# Main.net
KiCad netlist of a schematic drawn in Altium Designer
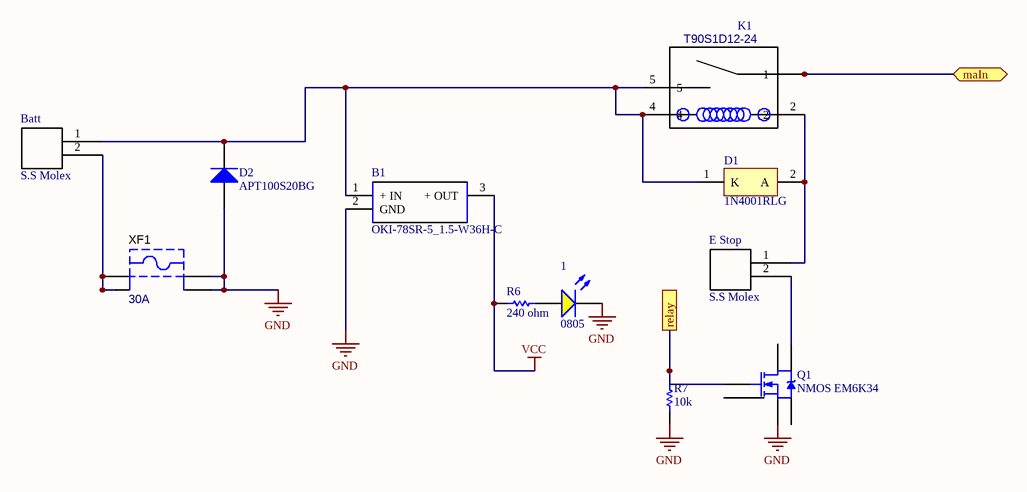
[diagram p0: Main.SchDoc]

(export (version "E")
  (design (tool "Eeschema 10.0.6"))
  (components
    (comp (ref "1")
      (value "0805")
      (footprint "LTST-C170YKT_V")
      (description "LED YELLOW CLEAR 0805 SMD")
      (fields (field (name "PARTNUMBER") "LTST-C170YKT"))
      (libsource (lib "Altium Content Vault") (part "LED_YELLOW_AC"))
    )
    (comp (ref "B1")
      (value "OKI-78SR-5_1.5-W36H-C")
      (footprint "OKI-78SR-HORIZONTAL")
      (description "Switching Regulator 7-36Vin 5Vo 1.5A Non-Isolated DC-DC Converter, 5V dc Output, 1.5A")
      (fields
        (field (name "MOUSER PART NUMBER") "580-OKI78SR51.5W36HC")
        (field (name "MANUFACTURER_PART_NUMBER") "OKI-78SR-5/1.5-W36H-C")
      )
      (libsource (lib "OKI-78SR-5_1.5-W36H-C") (part "OKI-78SR-5_1.5-W36H-C"))
    )
    (comp (ref "Batt")
      (value "S.S Molex")
      (footprint "1510482204")
      (description "Molex 6.5MM 2 pin connector, used for power connections. P/N 1510482204 and similar models.")
      (libsource (lib "24v connector") (part "Molex 6.5MM 2 pin connector"))
    )
    (comp (ref "D1")
      (value "1N4001RLG")
      (footprint "ONSC-AXIAL_LEAD-2-59-10_P")
      (description "Standard Recovery Rectifier, 2-Pin Axial_Lead, Pb-Free, Tape and Reel")
      (fields (field (name "MANUFACTURER") "On Semiconductor"))
      (libsource (lib "Altium Content Vault") (part "ONSC-D-K1A2-2_A"))
    )
    (comp (ref "D2")
      (value "APT100S20BG")
      (footprint "SMC")
      (description "Default Diode")
      (fields
        (field (name "PUBLISHER") "Altium Limited")
        (field (name "COMPONENTLINK1URL") "file:///C:/Users/Me/Downloads/Microsemi_APT100S20BG_High-Voltage_Schottky_Diode_Datasheet_D%20(1).PDF")
      )
      (libsource (lib "Miscellaneous Devices") (part "Diode"))
    )
    (comp (ref "E Stop")
      (value "S.S Molex")
      (footprint "1510482204")
      (description "Molex 6.5MM 2 pin connector, used for power connections. P/N 1510482204 and similar models.")
      (libsource (lib "24v connector") (part "Molex 6.5MM 2 pin connector"))
    )
    (comp (ref "K1")
      (value "T90S1D12-24")
      (footprint "TE_1-1393209-6")
      (fields (field (name "MF") "TE Connectivity"))
      (libsource (lib "1-1393209-6") (part "1-1393209-6"))
    )
    (comp (ref "Q1")
      (value "NMOS EM6K34")
      (footprint "*SOT50P160X55-6N")
      (description "N-Channel Power MOSFET")
      (fields (field (name "PUBLISHER") "Altium Limited"))
      (libsource (lib "Miscellaneous Devices") (part "NMOS-2"))
    )
    (comp (ref "R6")
      (value "240 ohm")
      (footprint "RESC0805(2012)_N")
      (description "160R 0.125W 1% 0805 (2012 Metric)  SMD")
      (fields (field (name "TOLERANCE") "1 %") (field (name "POWER") "0.125 W"))
      (libsource (lib "Altium Content Vault") (part "RES"))
    )
    (comp (ref "R7")
      (value "10k")
      (footprint "RESC0805(2012)_N")
      (description "160R 0.125W 1% 0805 (2012 Metric)  SMD")
      (fields (field (name "TOLERANCE") "1 %") (field (name "POWER") "0.125 W"))
      (libsource (lib "Altium Content Vault") (part "RES"))
    )
    (comp (ref "XF1")
      (value "30A")
      (footprint "KSTN-3568_V")
      (description "Fuse Holder, 30")
      (fields (field (name "MANUFACTURER") "Keystone"))
      (libsource (lib "Altium Content Vault") (part "FUSE_HOLDER-4"))
    )
  )
  (nets
    (net (code "1") (name "/maIn") (class "Default")
      (node (ref "K1") (pin "1") (pinfunction "1_1") (pintype "passive"))
      (node (ref "K1") (pin "3") (pinfunction "1_3") (pintype "passive"))
    )
    (net (code "2") (name "/relay") (class "Default")
      (node (ref "Q1") (pin "5") (pinfunction "G_5") (pintype "passive"))
      (node (ref "R7") (pin "2") (pinfunction "2_2") (pintype "passive"))
    )
    (net (code "3") (name "GND") (class "Default")
      (node (ref "1") (pin "C") (pinfunction "C_C") (pintype "passive"))
      (node (ref "B1") (pin "2") (pinfunction "GND_2") (pintype "passive"))
      (node (ref "D2") (pin "3") (pinfunction "A_3") (pintype "passive"))
      (node (ref "Q1") (pin "4") (pinfunction "S_4") (pintype "passive"))
      (node (ref "R7") (pin "1") (pinfunction "1_1") (pintype "passive"))
      (node (ref "XF1") (pin "3") (pinfunction "3_3") (pintype "passive"))
      (node (ref "XF1") (pin "4") (pinfunction "4_4") (pintype "passive"))
    )
    (net (code "4") (name "Net-(B1-+_IN)") (class "Default")
      (node (ref "B1") (pin "1") (pinfunction "+_IN_1") (pintype "passive"))
      (node (ref "Batt") (pin "1") (pintype "passive"))
      (node (ref "D1") (pin "1") (pinfunction "K_1") (pintype "passive"))
      (node (ref "D2") (pin "2") (pinfunction "K_2") (pintype "passive"))
      (node (ref "K1") (pin "4") (pinfunction "4_4") (pintype "passive"))
      (node (ref "K1") (pin "5") (pinfunction "5_5") (pintype "passive"))
    )
    (net (code "5") (name "Net-(Batt-Pad2)") (class "Default")
      (node (ref "Batt") (pin "2") (pintype "passive"))
      (node (ref "XF1") (pin "1") (pinfunction "1_1") (pintype "passive"))
      (node (ref "XF1") (pin "2") (pinfunction "2_2") (pintype "passive"))
    )
    (net (code "6") (name "Net-(D1-A)") (class "Default")
      (node (ref "D1") (pin "2") (pinfunction "A_2") (pintype "passive"))
      (node (ref "E Stop") (pin "1") (pintype "passive"))
      (node (ref "K1") (pin "2") (pinfunction "2_2") (pintype "passive"))
    )
    (net (code "7") (name "Net-(E Stop-Pad2)") (class "Default")
      (node (ref "E Stop") (pin "2") (pintype "passive"))
      (node (ref "Q1") (pin "3") (pinfunction "D_3") (pintype "passive"))
    )
    (net (code "8") (name "VCC") (class "Default")
      (node (ref "B1") (pin "3") (pinfunction "+_OUT_3") (pintype "passive"))
      (node (ref "R6") (pin "2") (pinfunction "2_2") (pintype "passive"))
    )
    (net (code "9") (name "unconnected-(1-PadA)") (class "Default")
      (node (ref "1") (pin "A") (pinfunction "A_A") (pintype "passive"))
    )
    (net (code "10") (name "unconnected-(Q1-D-Pad6)") (class "Default")
      (node (ref "Q1") (pin "6") (pinfunction "D_6") (pintype "passive"))
    )
    (net (code "11") (name "unconnected-(Q1-G-Pad2)") (class "Default")
      (node (ref "Q1") (pin "2") (pinfunction "G_2") (pintype "passive"))
    )
    (net (code "12") (name "unconnected-(Q1-S-Pad1)") (class "Default")
      (node (ref "Q1") (pin "1") (pinfunction "S_1") (pintype "passive"))
    )
    (net (code "13") (name "unconnected-(R6-Pad1)") (class "Default")
      (node (ref "R6") (pin "1") (pinfunction "1_1") (pintype "passive"))
    )
  )
)
